# 1-Schematic_WCP_Board.net
KiCad netlist of a schematic drawn in EasyEDA
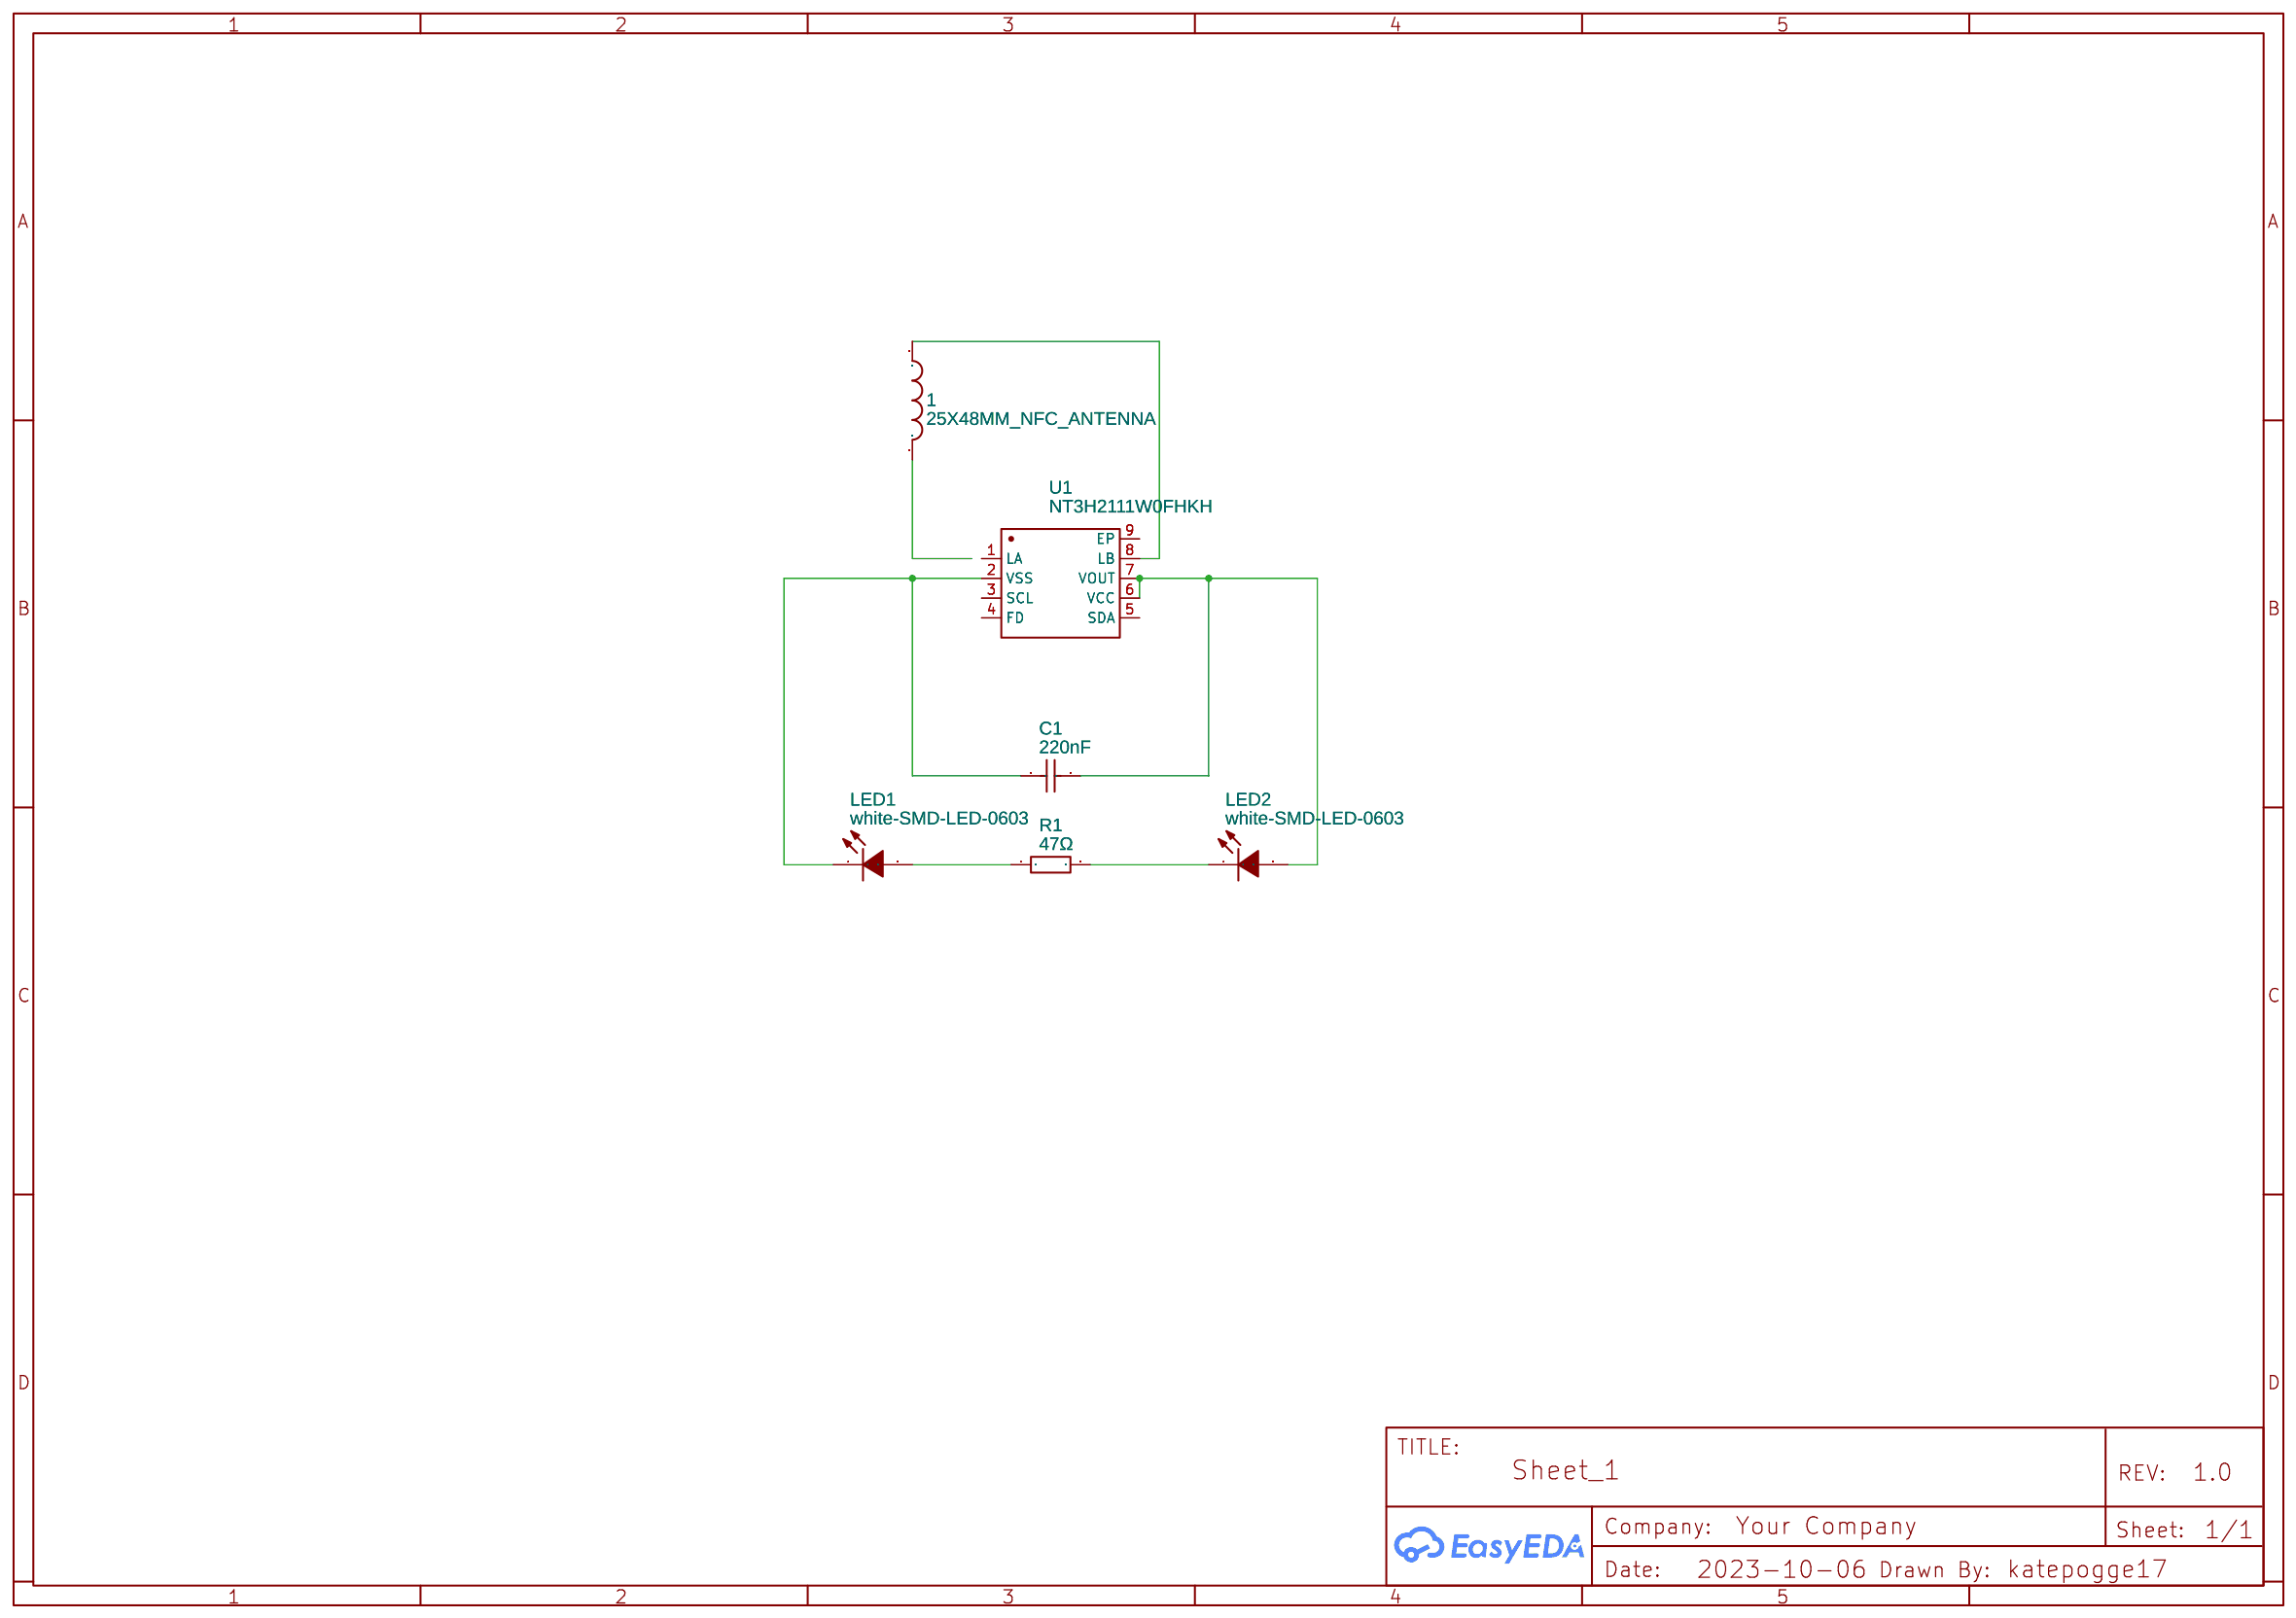
[diagram p0: schematic sheet]

(export (version "E")
  (design (tool "Eeschema 10.0.6"))
  (components
    (comp (ref "1") (value "25X48MM_NFC_ANTENNA") (libsource (lib "") (part "25X48MM_NFC_ANTENNA")))
    (comp (ref "C1")
      (value "220nF")
      (fields
        (field (name "Manufacturer Part") "CL10B224KA8NNNC")
        (field (name "Manufacturer") "SAMSUNG(三星)")
      )
      (libsource (lib "") (part "CL10B224KA8NNNC"))
    )
    (comp (ref "LED1")
      (value "white-SMD-LED-0603")
      (fields (field (name "Manufacturer Part") "白光贴片LED-0603"))
      (libsource (lib "") (part "white-SMD-LED-0603"))
    )
    (comp (ref "LED2")
      (value "white-SMD-LED-0603")
      (fields (field (name "Manufacturer Part") "白光贴片LED-0603"))
      (libsource (lib "") (part "white-SMD-LED-0603"))
    )
    (comp (ref "R1")
      (value "47Ω")
      (fields
        (field (name "Manufacturer Part") "0603WAF470JT5E")
        (field (name "Manufacturer") "UNI-ROYAL(厚声)")
      )
      (libsource (lib "") (part "0603WAF470JT5E"))
    )
    (comp (ref "U1")
      (value "NT3H2111W0FHKH")
      (fields (field (name "Manufacturer") "NXP(恩智浦)"))
      (libsource (lib "") (part "NT3H2111W0FHKH"))
    )
  )
  (nets
    (net (code "1") (name "Net-(LED1-A)") (class "Default")
      (node (ref "LED1") (pin "2") (pinfunction "A_2") (pintype "unspecified"))
      (node (ref "R1") (pin "1") (pinfunction "1_1") (pintype "input"))
    )
    (net (code "2") (name "Net-(LED1-K)") (class "Default")
      (node (ref "C1") (pin "1") (pinfunction "1_1") (pintype "input"))
      (node (ref "LED1") (pin "1") (pinfunction "K_1") (pintype "unspecified"))
      (node (ref "U1") (pin "2") (pinfunction "VSS_2") (pintype "unspecified"))
    )
    (net (code "3") (name "Net-(LED2-A)") (class "Default")
      (node (ref "C1") (pin "2") (pinfunction "2_2") (pintype "input"))
      (node (ref "LED2") (pin "2") (pinfunction "A_2") (pintype "unspecified"))
      (node (ref "U1") (pin "6") (pinfunction "VCC_6") (pintype "unspecified"))
      (node (ref "U1") (pin "7") (pinfunction "VOUT_7") (pintype "unspecified"))
    )
    (net (code "4") (name "Net-(LED2-K)") (class "Default")
      (node (ref "LED2") (pin "1") (pinfunction "K_1") (pintype "unspecified"))
      (node (ref "R1") (pin "2") (pinfunction "2_2") (pintype "input"))
    )
    (net (code "5") (name "Net-(U1-LB)") (class "Default")
      (node (ref "1") (pin "P$1") (pinfunction "P$1_P$1") (pintype "bidirectional"))
      (node (ref "U1") (pin "8") (pinfunction "LB_8") (pintype "unspecified"))
    )
    (net (code "6") (name "unconnected-(1-PadP$2)") (class "Default")
      (node (ref "1") (pin "P$2") (pinfunction "P$2_P$2") (pintype "bidirectional"))
    )
    (net (code "7") (name "unconnected-(U1-EP-Pad9)") (class "Default")
      (node (ref "U1") (pin "9") (pinfunction "EP_9") (pintype "unspecified"))
    )
    (net (code "8") (name "unconnected-(U1-FD-Pad4)") (class "Default")
      (node (ref "U1") (pin "4") (pinfunction "FD_4") (pintype "unspecified"))
    )
    (net (code "9") (name "unconnected-(U1-LA-Pad1)") (class "Default")
      (node (ref "U1") (pin "1") (pinfunction "LA_1") (pintype "unspecified"))
    )
    (net (code "10") (name "unconnected-(U1-SCL-Pad3)") (class "Default")
      (node (ref "U1") (pin "3") (pinfunction "SCL_3") (pintype "unspecified"))
    )
    (net (code "11") (name "unconnected-(U1-SDA-Pad5)") (class "Default")
      (node (ref "U1") (pin "5") (pinfunction "SDA_5") (pintype "unspecified"))
    )
  )
)
